# mdriver_slave.net
KiCad netlist of a schematic drawn in Altium Designer
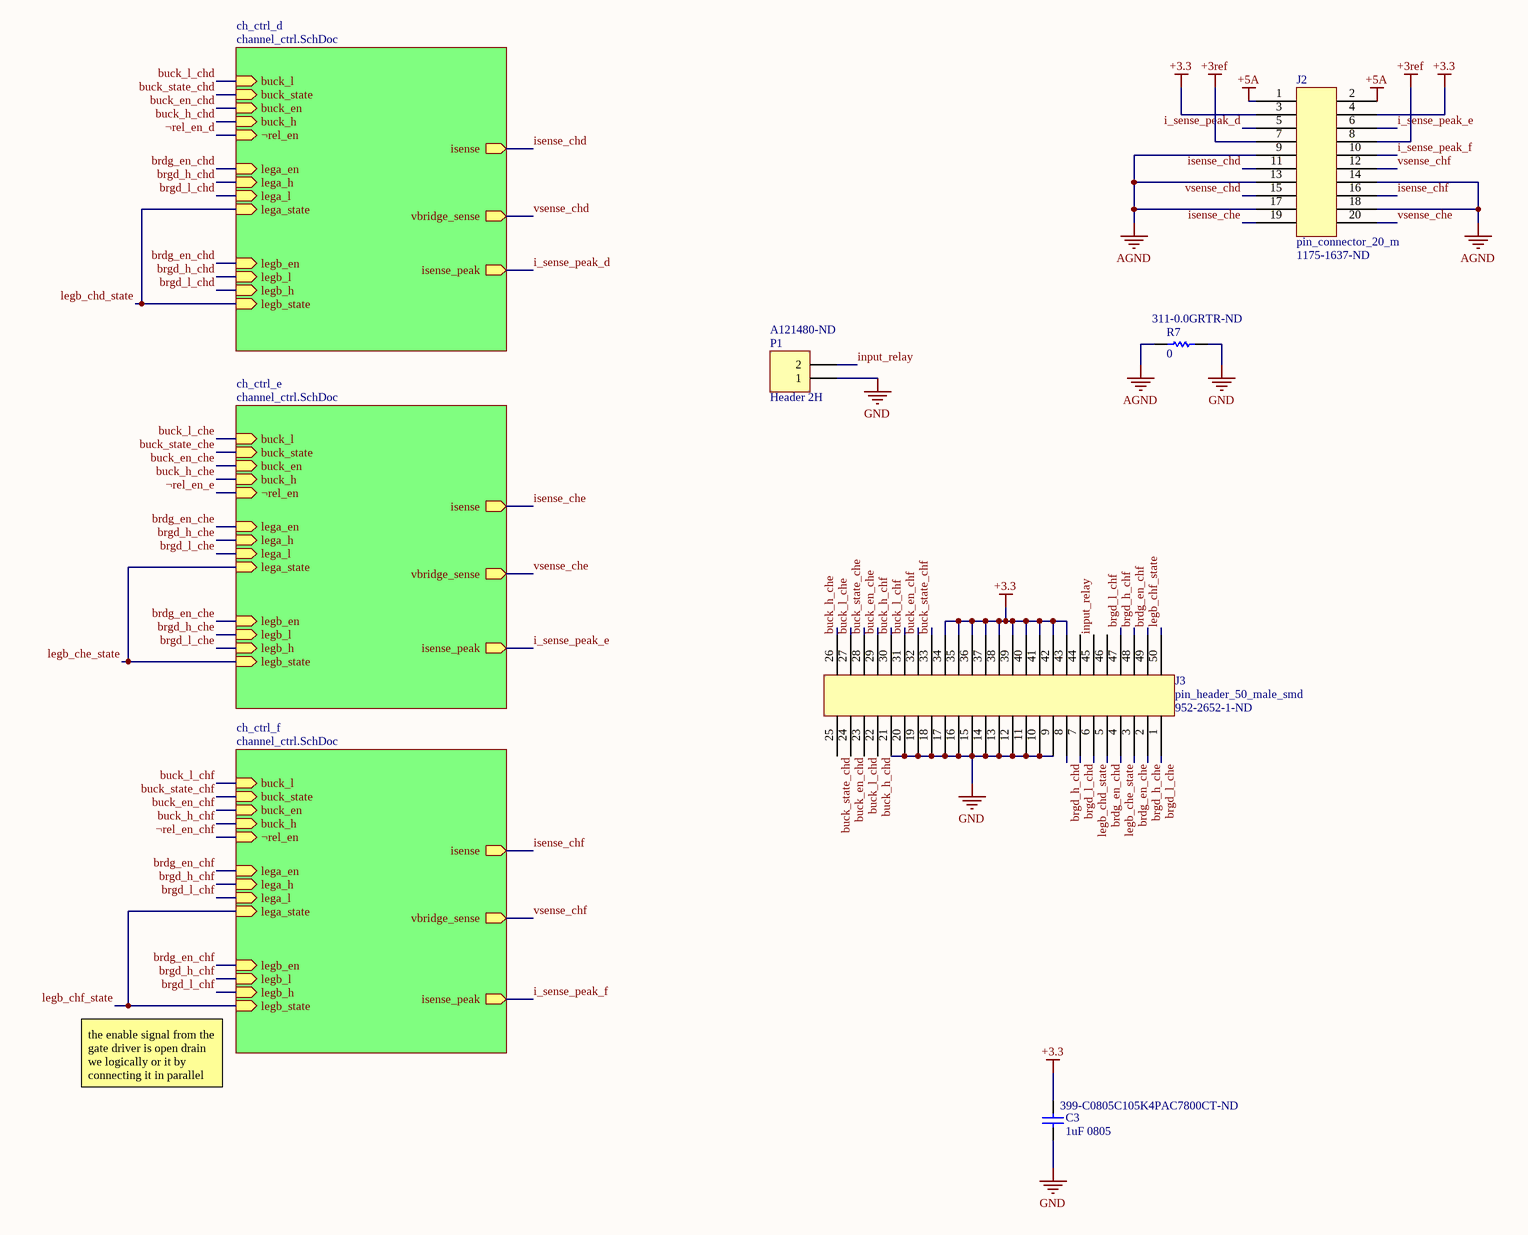
[diagram p0: mdriver_slave.SchDoc]

(export (version "E")
  (design (tool "Eeschema 10.0.6"))
  (components
    (comp (ref "C3")
      (value "1uF 0805")
      (footprint "Model Name")
      (description "Capacitor")
      (fields
        (field (name "SUPPLIER PART NUMBER 1") "399-C0805C105K4PAC7800CT-ND")
        (field (name "PUBLISHER") "Altium Limited")
      )
      (libsource (lib "Miscellaneous Devices") (part "Cap"))
    )
    (comp (ref "J2")
      (value "pin_connector_20_m")
      (footprint "PIN_20_MALE_3220-20-0300-00")
      (fields (field (name "SUPPLIER PART NUMBER 1") "1175-1637-ND"))
      (libsource (lib "coil_driver_lib") (part "pin_connector_20_m"))
    )
    (comp (ref "J3")
      (value "pin_header_50_male_smd")
      (footprint "pin_connector_50_m_1.27_smd")
      (description "Mating Product : 952-2565-ND")
      (fields (field (name "SUPPLIER PART NUMBER 1") "952-2652-1-ND"))
      (libsource (lib "coil_driver_lib") (part "pin_header_50_male_smd"))
    )
    (comp (ref "P1")
      (value "Header 2H")
      (footprint "HEADER_1_2_f")
      (description "Header, 2-Pin, Right Angle")
      (fields
        (field (name "SUPPLIER PART NUMBER 1") "A121480-ND")
        (field (name "PUBLISHER") "Altium Limited")
      )
      (libsource (lib "Miscellaneous Connectors") (part "Header 2H"))
    )
    (comp (ref "R7")
      (value "0")
      (footprint "RES 0603_1608")
      (description "Resistor")
      (fields
        (field (name "SUPPLIER PART NUMBER 1") "311-0.0GRTR-ND")
        (field (name "PUBLISHER") "Altium Limited")
      )
      (libsource (lib "Miscellaneous Devices") (part "Res1"))
    )
  )
  (nets
    (net (code "1") (name "+3.3") (class "Default")
      (node (ref "C3") (pin "2") (pinfunction "2_2") (pintype "passive"))
      (node (ref "J2") (pin "3") (pintype "passive"))
      (node (ref "J2") (pin "4") (pintype "passive"))
      (node (ref "J3") (pin "34") (pintype "passive"))
      (node (ref "J3") (pin "35") (pintype "passive"))
      (node (ref "J3") (pin "36") (pintype "passive"))
      (node (ref "J3") (pin "37") (pintype "passive"))
      (node (ref "J3") (pin "38") (pintype "passive"))
      (node (ref "J3") (pin "39") (pintype "passive"))
      (node (ref "J3") (pin "40") (pintype "passive"))
      (node (ref "J3") (pin "41") (pintype "passive"))
      (node (ref "J3") (pin "42") (pintype "passive"))
      (node (ref "J3") (pin "43") (pintype "passive"))
    )
    (net (code "2") (name "+3ref") (class "Default")
      (node (ref "J2") (pin "7") (pintype "passive"))
      (node (ref "J2") (pin "8") (pintype "passive"))
    )
    (net (code "3") (name "+5A") (class "Default")
      (node (ref "J2") (pin "1") (pintype "passive"))
      (node (ref "J2") (pin "2") (pintype "passive"))
    )
    (net (code "4") (name "/brdg_en_chd") (class "Default") (node (ref "J3") (pin "5") (pintype "passive")))
    (net (code "5") (name "/brdg_en_che") (class "Default") (node (ref "J3") (pin "3") (pintype "passive")))
    (net (code "6") (name "/brdg_en_chf") (class "Default") (node (ref "J3") (pin "49") (pintype "passive")))
    (net (code "7") (name "/brgd_h_chd") (class "Default") (node (ref "J3") (pin "8") (pintype "passive")))
    (net (code "8") (name "/brgd_h_che") (class "Default") (node (ref "J3") (pin "2") (pintype "passive")))
    (net (code "9") (name "/brgd_h_chf") (class "Default") (node (ref "J3") (pin "48") (pintype "passive")))
    (net (code "10") (name "/brgd_l_chd") (class "Default") (node (ref "J3") (pin "7") (pintype "passive")))
    (net (code "11") (name "/brgd_l_che") (class "Default") (node (ref "J3") (pin "1") (pintype "passive")))
    (net (code "12") (name "/brgd_l_chf") (class "Default") (node (ref "J3") (pin "47") (pintype "passive")))
    (net (code "13") (name "/buck_en_chd") (class "Default") (node (ref "J3") (pin "24") (pintype "passive")))
    (net (code "14") (name "/buck_en_che") (class "Default") (node (ref "J3") (pin "29") (pintype "passive")))
    (net (code "15") (name "/buck_en_chf") (class "Default") (node (ref "J3") (pin "32") (pintype "passive")))
    (net (code "16") (name "/buck_h_chd") (class "Default") (node (ref "J3") (pin "22") (pintype "passive")))
    (net (code "17") (name "/buck_h_che") (class "Default") (node (ref "J3") (pin "26") (pintype "passive")))
    (net (code "18") (name "/buck_h_chf") (class "Default") (node (ref "J3") (pin "30") (pintype "passive")))
    (net (code "19") (name "/buck_l_chd") (class "Default") (node (ref "J3") (pin "23") (pintype "passive")))
    (net (code "20") (name "/buck_l_che") (class "Default") (node (ref "J3") (pin "27") (pintype "passive")))
    (net (code "21") (name "/buck_l_chf") (class "Default") (node (ref "J3") (pin "31") (pintype "passive")))
    (net (code "22") (name "/buck_state_chd") (class "Default")
      (node (ref "J3") (pin "25") (pintype "passive"))
    )
    (net (code "23") (name "/buck_state_che") (class "Default")
      (node (ref "J3") (pin "28") (pintype "passive"))
    )
    (net (code "24") (name "/buck_state_chf") (class "Default")
      (node (ref "J3") (pin "33") (pintype "passive"))
    )
    (net (code "25") (name "/i_sense_peak_d") (class "Default")
      (node (ref "J2") (pin "5") (pintype "passive"))
    )
    (net (code "26") (name "/i_sense_peak_e") (class "Default")
      (node (ref "J2") (pin "6") (pintype "passive"))
    )
    (net (code "27") (name "/i_sense_peak_f") (class "Default")
      (node (ref "J2") (pin "10") (pintype "passive"))
    )
    (net (code "28") (name "/input_relay") (class "Default")
      (node (ref "J3") (pin "45") (pintype "passive"))
      (node (ref "P1") (pin "2") (pinfunction "2_2") (pintype "passive"))
    )
    (net (code "29") (name "/isense_chd") (class "Default") (node (ref "J2") (pin "11") (pintype "passive")))
    (net (code "30") (name "/isense_che") (class "Default") (node (ref "J2") (pin "19") (pintype "passive")))
    (net (code "31") (name "/isense_chf") (class "Default") (node (ref "J2") (pin "16") (pintype "passive")))
    (net (code "32") (name "/legb_chd_state") (class "Default")
      (node (ref "J3") (pin "6") (pintype "passive"))
    )
    (net (code "33") (name "/legb_che_state") (class "Default")
      (node (ref "J3") (pin "4") (pintype "passive"))
    )
    (net (code "34") (name "/legb_chf_state") (class "Default")
      (node (ref "J3") (pin "50") (pintype "passive"))
    )
    (net (code "35") (name "/vsense_chd") (class "Default") (node (ref "J2") (pin "15") (pintype "passive")))
    (net (code "36") (name "/vsense_che") (class "Default") (node (ref "J2") (pin "20") (pintype "passive")))
    (net (code "37") (name "/vsense_chf") (class "Default") (node (ref "J2") (pin "12") (pintype "passive")))
    (net (code "41") (name "AGND") (class "Default")
      (node (ref "J2") (pin "13") (pintype "passive"))
      (node (ref "J2") (pin "14") (pintype "passive"))
      (node (ref "J2") (pin "17") (pintype "passive"))
      (node (ref "J2") (pin "18") (pintype "passive"))
      (node (ref "J2") (pin "9") (pintype "passive"))
      (node (ref "R7") (pin "1") (pinfunction "1_1") (pintype "passive"))
    )
    (net (code "42") (name "GND") (class "Default")
      (node (ref "C3") (pin "1") (pinfunction "1_1") (pintype "passive"))
      (node (ref "J3") (pin "10") (pintype "passive"))
      (node (ref "J3") (pin "11") (pintype "passive"))
      (node (ref "J3") (pin "12") (pintype "passive"))
      (node (ref "J3") (pin "13") (pintype "passive"))
      (node (ref "J3") (pin "14") (pintype "passive"))
      (node (ref "J3") (pin "15") (pintype "passive"))
      (node (ref "J3") (pin "16") (pintype "passive"))
      (node (ref "J3") (pin "17") (pintype "passive"))
      (node (ref "J3") (pin "18") (pintype "passive"))
      (node (ref "J3") (pin "19") (pintype "passive"))
      (node (ref "J3") (pin "20") (pintype "passive"))
      (node (ref "J3") (pin "21") (pintype "passive"))
      (node (ref "J3") (pin "9") (pintype "passive"))
      (node (ref "P1") (pin "1") (pinfunction "1_1") (pintype "passive"))
      (node (ref "R7") (pin "2") (pinfunction "2_2") (pintype "passive"))
    )
    (net (code "43") (name "unconnected-(J3-Pad44)") (class "Default")
      (node (ref "J3") (pin "44") (pintype "passive"))
    )
    (net (code "44") (name "unconnected-(J3-Pad46)") (class "Default")
      (node (ref "J3") (pin "46") (pintype "passive"))
    )
  )
)
